# AUDIO_CODEC.net
KiCad netlist of a schematic drawn in Altium Designer
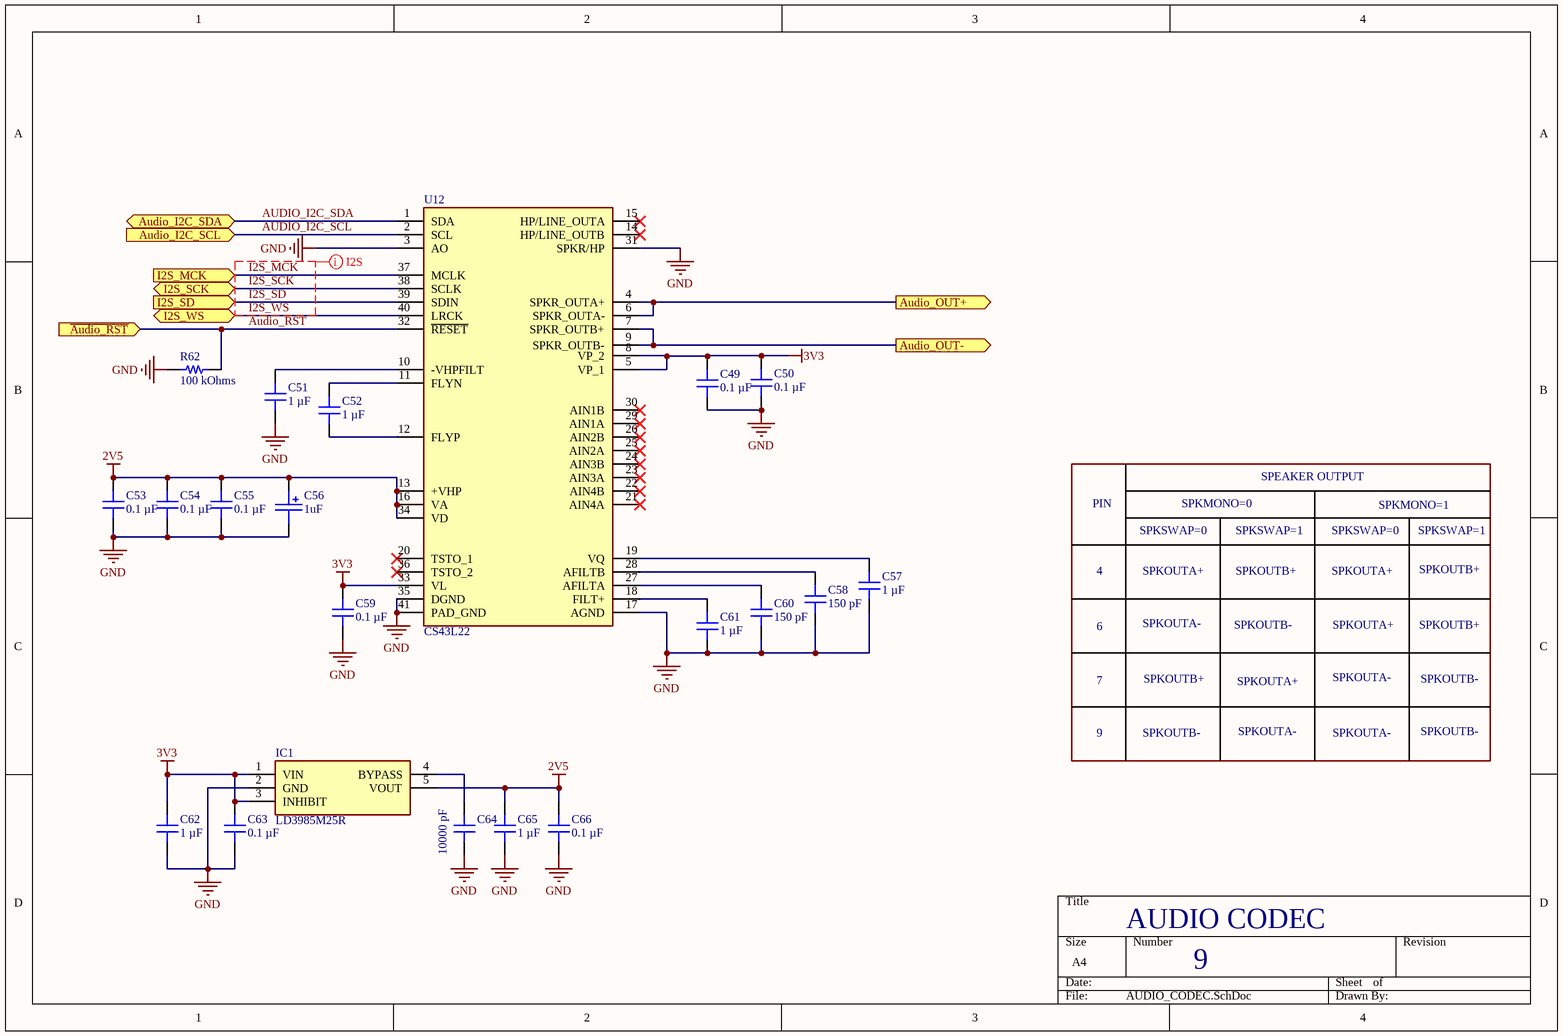
[diagram p0: AUDIO_CODEC.SchDoc]

(export (version "E")
  (design (tool "Eeschema 10.0.6"))
  (components
    (comp (ref "C49")
      (value "0.1 µF")
      (footprint "CAP 0402_1005")
      (description "CAP CER 0.1UF 16V X7R 0402")
      (fields (field (name "PART NUMBER") "CC0402KRX7R7BB104") (field (name "MANUFACTURER") "Yageo"))
      (libsource (lib "Celestial Altium Library") (part "Capacitor"))
    )
    (comp (ref "C50")
      (value "0.1 µF")
      (footprint "CAP 0402_1005")
      (description "CAP CER 0.1UF 16V X7R 0402")
      (fields (field (name "PART NUMBER") "CC0402KRX7R7BB104") (field (name "MANUFACTURER") "Yageo"))
      (libsource (lib "Celestial Altium Library") (part "Capacitor"))
    )
    (comp (ref "C51")
      (value "1 µF")
      (footprint "CAP 0603_1608")
      (description "CAP CER 1UF 16V X5R 0603")
      (fields (field (name "PART NUMBER") "CC0603KRX5R7BB105") (field (name "MANUFACTURER") "Yageo"))
      (libsource (lib "Celestial Altium Library") (part "Capacitor"))
    )
    (comp (ref "C52")
      (value "1 µF")
      (footprint "CAP 0603_1608")
      (description "CAP CER 1UF 16V X5R 0603")
      (fields (field (name "PART NUMBER") "CC0603KRX5R7BB105") (field (name "MANUFACTURER") "Yageo"))
      (libsource (lib "Celestial Altium Library") (part "Capacitor"))
    )
    (comp (ref "C53")
      (value "0.1 µF")
      (footprint "CAP 0402_1005")
      (description "CAP CER 0.1UF 16V X7R 0402")
      (fields (field (name "PART NUMBER") "CC0402KRX7R7BB104") (field (name "MANUFACTURER") "Yageo"))
      (libsource (lib "Celestial Altium Library") (part "Capacitor"))
    )
    (comp (ref "C54")
      (value "0.1 µF")
      (footprint "CAP 0402_1005")
      (description "CAP CER 0.1UF 16V X7R 0402")
      (fields (field (name "PART NUMBER") "CC0402KRX7R7BB104") (field (name "MANUFACTURER") "Yageo"))
      (libsource (lib "Celestial Altium Library") (part "Capacitor"))
    )
    (comp (ref "C55")
      (value "0.1 µF")
      (footprint "CAP 0402_1005")
      (description "CAP CER 0.1UF 16V X7R 0402")
      (fields (field (name "PART NUMBER") "CC0402KRX7R7BB104") (field (name "MANUFACTURER") "Yageo"))
      (libsource (lib "Celestial Altium Library") (part "Capacitor"))
    )
    (comp (ref "C56")
      (value "1uF")
      (footprint "TATAJA105K016R")
      (description "Tantalum Capacitors - Solid SMD 16V 1uF 10%")
      (libsource (lib "SMALL_BCM") (part "TAJA105K016R"))
    )
    (comp (ref "C57")
      (value "1 µF")
      (footprint "CAP 0603_1608")
      (description "CAP CER 1UF 16V X5R 0603")
      (fields (field (name "PART NUMBER") "CC0603KRX5R7BB105") (field (name "MANUFACTURER") "Yageo"))
      (libsource (lib "Celestial Altium Library") (part "Capacitor"))
    )
    (comp (ref "C58")
      (value "150 pF")
      (footprint "CAP 0603_1608")
      (description "CAP CER 150PF 50V C0G/NPO 0603")
      (fields (field (name "PART NUMBER") "CC0603JRNPO9BN151") (field (name "MANUFACTURER") "Yageo"))
      (libsource (lib "Celestial Altium Library") (part "Capacitor"))
    )
    (comp (ref "C59")
      (value "0.1 µF")
      (footprint "CAP 0402_1005")
      (description "CAP CER 0.1UF 16V X7R 0402")
      (fields (field (name "PART NUMBER") "CC0402KRX7R7BB104") (field (name "MANUFACTURER") "Yageo"))
      (libsource (lib "Celestial Altium Library") (part "Capacitor"))
    )
    (comp (ref "C60")
      (value "150 pF")
      (footprint "CAP 0603_1608")
      (description "CAP CER 150PF 50V C0G/NPO 0603")
      (fields (field (name "PART NUMBER") "CC0603JRNPO9BN151") (field (name "MANUFACTURER") "Yageo"))
      (libsource (lib "Celestial Altium Library") (part "Capacitor"))
    )
    (comp (ref "C61")
      (value "1 µF")
      (footprint "CAP 0603_1608")
      (description "CAP CER 1UF 16V X5R 0603")
      (fields (field (name "PART NUMBER") "CC0603KRX5R7BB105") (field (name "MANUFACTURER") "Yageo"))
      (libsource (lib "Celestial Altium Library") (part "Capacitor"))
    )
    (comp (ref "C62")
      (value "1 µF")
      (footprint "CAP 0603_1608")
      (description "CAP CER 1UF 16V X5R 0603")
      (fields (field (name "PART NUMBER") "CC0603KRX5R7BB105") (field (name "MANUFACTURER") "Yageo"))
      (libsource (lib "Celestial Altium Library") (part "Capacitor"))
    )
    (comp (ref "C63")
      (value "0.1 µF")
      (footprint "CAP 0402_1005")
      (description "CAP CER 0.1UF 16V X7R 0402")
      (fields (field (name "PART NUMBER") "CC0402KRX7R7BB104") (field (name "MANUFACTURER") "Yageo"))
      (libsource (lib "Celestial Altium Library") (part "Capacitor"))
    )
    (comp (ref "C64")
      (value "10000 pF")
      (footprint "CAP 0603_1608")
      (description "CAP CER 10000PF 50V X7R 0603")
      (fields (field (name "PART NUMBER") "CC0603KRX7R9BB103") (field (name "MANUFACTURER") "Yageo"))
      (libsource (lib "Celestial Altium Library") (part "Capacitor"))
    )
    (comp (ref "C65")
      (value "1 µF")
      (footprint "CAP 0603_1608")
      (description "CAP CER 1UF 16V X5R 0603")
      (fields (field (name "PART NUMBER") "CC0603KRX5R7BB105") (field (name "MANUFACTURER") "Yageo"))
      (libsource (lib "Celestial Altium Library") (part "Capacitor"))
    )
    (comp (ref "C66")
      (value "0.1 µF")
      (footprint "CAP 0402_1005")
      (description "CAP CER 0.1UF 16V X7R 0402")
      (fields (field (name "PART NUMBER") "CC0402KRX7R7BB104") (field (name "MANUFACTURER") "Yageo"))
      (libsource (lib "Celestial Altium Library") (part "Capacitor"))
    )
    (comp (ref "IC1")
      (value "LD3985M25R")
      (footprint "SamacSys:SOT95P280X145-5N")
      (description "Integrated Circuit")
      (fields (field (name "MOUSER PART NUMBER") "511-LD3985M25R"))
      (libsource (lib "*") (part "LD3985M25R"))
    )
    (comp (ref "R62")
      (value "100 kOhms")
      (footprint "RES 0603_1608")
      (description "RES 100K OHM 5% 1/10W 0603")
      (fields
        (field (name "PART NUMBER") "RMCF0603JT100K")
        (field (name "MANUFACTURER") "Stackpole Electronics Inc")
      )
      (libsource (lib "Celestial Altium Library") (part "Resistor"))
    )
    (comp (ref "U12")
      (value "CS43L22")
      (footprint "QFN50P600X600X100-41N-D")
      (description "IC DAC/AUDIO 24BIT 96K 40QFN")
      (libsource (lib "SMALL_BCM") (part "CS43L22-CNZ"))
    )
  )
  (nets
    (net (code "1") (name "/AUDIO_I2C_SCL") (class "Default")
      (node (ref "U12") (pin "2") (pinfunction "SCL_2") (pintype "passive"))
    )
    (net (code "2") (name "/AUDIO_I2C_SDA") (class "Default")
      (node (ref "U12") (pin "1") (pinfunction "SDA_1") (pintype "passive"))
    )
    (net (code "3") (name "/Audio_OUT+") (class "Default")
      (node (ref "U12") (pin "4") (pinfunction "SPKR_OUTA+_4") (pintype "passive"))
      (node (ref "U12") (pin "6") (pinfunction "SPKR_OUTA-_6") (pintype "passive"))
    )
    (net (code "4") (name "/Audio_OUT-") (class "Default")
      (node (ref "U12") (pin "7") (pinfunction "SPKR_OUTB+_7") (pintype "passive"))
      (node (ref "U12") (pin "9") (pinfunction "SPKR_OUTB-_9") (pintype "passive"))
    )
    (net (code "5") (name "/Audio_RST") (class "Default")
      (node (ref "R62") (pin "2") (pinfunction "2_2") (pintype "passive"))
      (node (ref "U12") (pin "32") (pinfunction "~{RESET}_32") (pintype "passive"))
    )
    (net (code "6") (name "/I2S_MCK") (class "Default")
      (node (ref "U12") (pin "37") (pinfunction "MCLK_37") (pintype "passive"))
    )
    (net (code "7") (name "/I2S_SCK") (class "Default")
      (node (ref "U12") (pin "38") (pinfunction "SCLK_38") (pintype "passive"))
    )
    (net (code "8") (name "/I2S_SD") (class "Default")
      (node (ref "U12") (pin "39") (pinfunction "SDIN_39") (pintype "passive"))
    )
    (net (code "9") (name "/I2S_WS") (class "Default")
      (node (ref "U12") (pin "40") (pinfunction "LRCK_40") (pintype "passive"))
    )
    (net (code "10") (name "2V5") (class "Default")
      (node (ref "C53") (pin "2") (pinfunction "2_2") (pintype "passive"))
      (node (ref "C54") (pin "2") (pinfunction "2_2") (pintype "passive"))
      (node (ref "C55") (pin "2") (pinfunction "2_2") (pintype "passive"))
      (node (ref "C56") (pin "1") (pinfunction "+_1") (pintype "passive"))
      (node (ref "C65") (pin "2") (pinfunction "2_2") (pintype "passive"))
      (node (ref "C66") (pin "2") (pinfunction "2_2") (pintype "passive"))
      (node (ref "IC1") (pin "5") (pinfunction "VOUT_5") (pintype "passive"))
      (node (ref "U12") (pin "13") (pinfunction "+VHP_13") (pintype "passive"))
      (node (ref "U12") (pin "16") (pinfunction "VA_16") (pintype "passive"))
      (node (ref "U12") (pin "34") (pinfunction "VD_34") (pintype "passive"))
    )
    (net (code "11") (name "3V3") (class "Default")
      (node (ref "C49") (pin "2") (pinfunction "2_2") (pintype "passive"))
      (node (ref "C50") (pin "2") (pinfunction "2_2") (pintype "passive"))
      (node (ref "C59") (pin "2") (pinfunction "2_2") (pintype "passive"))
      (node (ref "C62") (pin "2") (pinfunction "2_2") (pintype "passive"))
      (node (ref "C63") (pin "2") (pinfunction "2_2") (pintype "passive"))
      (node (ref "IC1") (pin "1") (pinfunction "VIN_1") (pintype "passive"))
      (node (ref "IC1") (pin "3") (pinfunction "INHIBIT_3") (pintype "passive"))
      (node (ref "U12") (pin "33") (pinfunction "VL_33") (pintype "passive"))
      (node (ref "U12") (pin "5") (pinfunction "VP_1_5") (pintype "passive"))
      (node (ref "U12") (pin "8") (pinfunction "VP_2_8") (pintype "passive"))
    )
    (net (code "12") (name "GND") (class "Default")
      (node (ref "C49") (pin "1") (pinfunction "1_1") (pintype "passive"))
      (node (ref "C50") (pin "1") (pinfunction "1_1") (pintype "passive"))
      (node (ref "C51") (pin "1") (pinfunction "1_1") (pintype "passive"))
      (node (ref "C53") (pin "1") (pinfunction "1_1") (pintype "passive"))
      (node (ref "C54") (pin "1") (pinfunction "1_1") (pintype "passive"))
      (node (ref "C55") (pin "1") (pinfunction "1_1") (pintype "passive"))
      (node (ref "C56") (pin "2") (pinfunction "-_2") (pintype "passive"))
      (node (ref "C57") (pin "1") (pinfunction "1_1") (pintype "passive"))
      (node (ref "C58") (pin "1") (pinfunction "1_1") (pintype "passive"))
      (node (ref "C59") (pin "1") (pinfunction "1_1") (pintype "passive"))
      (node (ref "C60") (pin "1") (pinfunction "1_1") (pintype "passive"))
      (node (ref "C61") (pin "1") (pinfunction "1_1") (pintype "passive"))
      (node (ref "C62") (pin "1") (pinfunction "1_1") (pintype "passive"))
      (node (ref "C63") (pin "1") (pinfunction "1_1") (pintype "passive"))
      (node (ref "C64") (pin "1") (pinfunction "1_1") (pintype "passive"))
      (node (ref "C65") (pin "1") (pinfunction "1_1") (pintype "passive"))
      (node (ref "C66") (pin "1") (pinfunction "1_1") (pintype "passive"))
      (node (ref "IC1") (pin "2") (pinfunction "GND_2") (pintype "passive"))
      (node (ref "R62") (pin "1") (pinfunction "1_1") (pintype "passive"))
      (node (ref "U12") (pin "17") (pinfunction "AGND_17") (pintype "passive"))
      (node (ref "U12") (pin "3") (pinfunction "AO_3") (pintype "passive"))
      (node (ref "U12") (pin "31") (pinfunction "SPKR/HP_31") (pintype "passive"))
      (node (ref "U12") (pin "35") (pinfunction "DGND_35") (pintype "passive"))
      (node (ref "U12") (pin "41") (pinfunction "PAD_GND_41") (pintype "passive"))
    )
    (net (code "13") (name "Net-(IC1-BYPASS)") (class "Default")
      (node (ref "C64") (pin "2") (pinfunction "2_2") (pintype "passive"))
      (node (ref "IC1") (pin "4") (pinfunction "BYPASS_4") (pintype "passive"))
    )
    (net (code "14") (name "Net-(U12--VHPFILT)") (class "Default")
      (node (ref "C51") (pin "2") (pinfunction "2_2") (pintype "passive"))
      (node (ref "U12") (pin "10") (pinfunction "-VHPFILT_10") (pintype "passive"))
    )
    (net (code "15") (name "Net-(U12-AFILTA)") (class "Default")
      (node (ref "C60") (pin "2") (pinfunction "2_2") (pintype "passive"))
      (node (ref "U12") (pin "27") (pinfunction "AFILTA_27") (pintype "passive"))
    )
    (net (code "16") (name "Net-(U12-AFILTB)") (class "Default")
      (node (ref "C58") (pin "2") (pinfunction "2_2") (pintype "passive"))
      (node (ref "U12") (pin "28") (pinfunction "AFILTB_28") (pintype "passive"))
    )
    (net (code "17") (name "Net-(U12-FILT+)") (class "Default")
      (node (ref "C61") (pin "2") (pinfunction "2_2") (pintype "passive"))
      (node (ref "U12") (pin "18") (pinfunction "FILT+_18") (pintype "passive"))
    )
    (net (code "18") (name "Net-(U12-FLYN)") (class "Default")
      (node (ref "C52") (pin "2") (pinfunction "2_2") (pintype "passive"))
      (node (ref "U12") (pin "11") (pinfunction "FLYN_11") (pintype "passive"))
    )
    (net (code "19") (name "Net-(U12-FLYP)") (class "Default")
      (node (ref "C52") (pin "1") (pinfunction "1_1") (pintype "passive"))
      (node (ref "U12") (pin "12") (pinfunction "FLYP_12") (pintype "passive"))
    )
    (net (code "20") (name "Net-(U12-VQ)") (class "Default")
      (node (ref "C57") (pin "2") (pinfunction "2_2") (pintype "passive"))
      (node (ref "U12") (pin "19") (pinfunction "VQ_19") (pintype "passive"))
    )
    (net (code "21") (name "unconnected-(U12-AIN1A-Pad29)") (class "Default")
      (node (ref "U12") (pin "29") (pinfunction "AIN1A_29") (pintype "passive+no_connect"))
    )
    (net (code "22") (name "unconnected-(U12-AIN1B-Pad30)") (class "Default")
      (node (ref "U12") (pin "30") (pinfunction "AIN1B_30") (pintype "passive+no_connect"))
    )
    (net (code "23") (name "unconnected-(U12-AIN2A-Pad25)") (class "Default")
      (node (ref "U12") (pin "25") (pinfunction "AIN2A_25") (pintype "passive+no_connect"))
    )
    (net (code "24") (name "unconnected-(U12-AIN2B-Pad26)") (class "Default")
      (node (ref "U12") (pin "26") (pinfunction "AIN2B_26") (pintype "passive+no_connect"))
    )
    (net (code "25") (name "unconnected-(U12-AIN3A-Pad23)") (class "Default")
      (node (ref "U12") (pin "23") (pinfunction "AIN3A_23") (pintype "passive+no_connect"))
    )
    (net (code "26") (name "unconnected-(U12-AIN3B-Pad24)") (class "Default")
      (node (ref "U12") (pin "24") (pinfunction "AIN3B_24") (pintype "passive+no_connect"))
    )
    (net (code "27") (name "unconnected-(U12-AIN4A-Pad21)") (class "Default")
      (node (ref "U12") (pin "21") (pinfunction "AIN4A_21") (pintype "passive+no_connect"))
    )
    (net (code "28") (name "unconnected-(U12-AIN4B-Pad22)") (class "Default")
      (node (ref "U12") (pin "22") (pinfunction "AIN4B_22") (pintype "passive+no_connect"))
    )
    (net (code "29") (name "unconnected-(U12-HP{slash}LINE_OUTA-Pad15)") (class "Default")
      (node (ref "U12") (pin "15") (pinfunction "HP/LINE_OUTA_15") (pintype "passive+no_connect"))
    )
    (net (code "30") (name "unconnected-(U12-HP{slash}LINE_OUTB-Pad14)") (class "Default")
      (node (ref "U12") (pin "14") (pinfunction "HP/LINE_OUTB_14") (pintype "passive+no_connect"))
    )
    (net (code "31") (name "unconnected-(U12-TSTO_1-Pad20)") (class "Default")
      (node (ref "U12") (pin "20") (pinfunction "TSTO_1_20") (pintype "passive+no_connect"))
    )
    (net (code "32") (name "unconnected-(U12-TSTO_2-Pad36)") (class "Default")
      (node (ref "U12") (pin "36") (pinfunction "TSTO_2_36") (pintype "passive+no_connect"))
    )
  )
)
